# QCopterMV_CAMSPI_Sch.net
KiCad netlist of a schematic drawn in Altium Designer
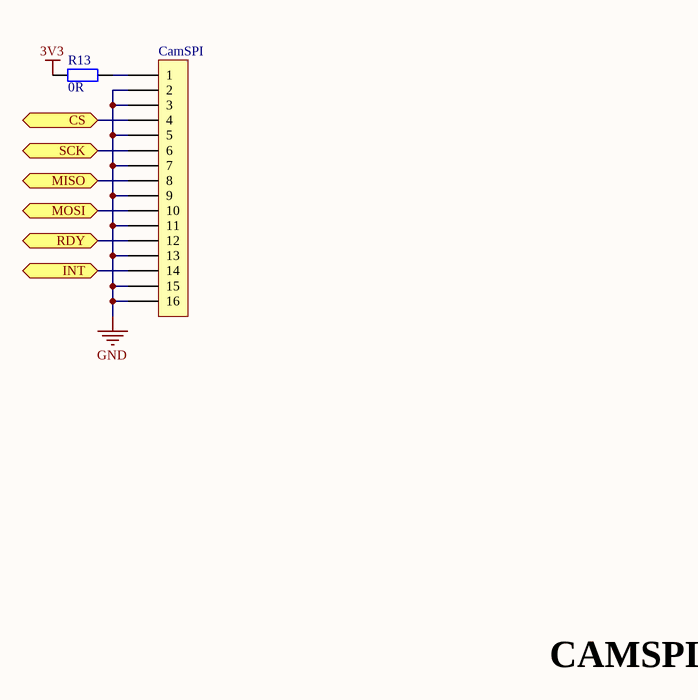
[diagram p0: QCopterMV_CAMSPI_Sch.SchDoc]

(export (version "E")
  (design (tool "Eeschema 10.0.6"))
  (components
    (comp (ref "CamSPI")
      (value "FFC_0.5_16")
      (footprint "PCB_Connector:FFC_0.5_16")
      (description "FFC")
      (libsource (lib "SCH_Connector") (part "FFC_0.5_16"))
    )
    (comp (ref "R13")
      (value "0R")
      (footprint "PCB_Passive:RES_0603")
      (description "Resistor")
      (fields (field (name "Comment") "Res_0603"))
      (libsource (lib "SCH_Passive") (part "Res_0603"))
    )
  )
  (nets
    (net (code "1") (name "/CS") (class "Default")
      (node (ref "CamSPI") (pin "4") (pinfunction "4_4") (pintype "passive"))
    )
    (net (code "2") (name "/INT") (class "Default")
      (node (ref "CamSPI") (pin "14") (pinfunction "14_14") (pintype "passive"))
    )
    (net (code "3") (name "/MISO") (class "Default")
      (node (ref "CamSPI") (pin "8") (pinfunction "8_8") (pintype "passive"))
    )
    (net (code "4") (name "/MOSI") (class "Default")
      (node (ref "CamSPI") (pin "10") (pinfunction "10_10") (pintype "passive"))
    )
    (net (code "5") (name "/RDY") (class "Default")
      (node (ref "CamSPI") (pin "12") (pinfunction "12_12") (pintype "passive"))
    )
    (net (code "6") (name "/SCK") (class "Default")
      (node (ref "CamSPI") (pin "6") (pinfunction "6_6") (pintype "passive"))
    )
    (net (code "7") (name "3V3") (class "Default")
      (node (ref "R13") (pin "1") (pinfunction "1_1") (pintype "passive"))
    )
    (net (code "8") (name "GND") (class "Default")
      (node (ref "CamSPI") (pin "11") (pinfunction "11_11") (pintype "passive"))
      (node (ref "CamSPI") (pin "13") (pinfunction "13_13") (pintype "passive"))
      (node (ref "CamSPI") (pin "15") (pinfunction "15_15") (pintype "passive"))
      (node (ref "CamSPI") (pin "16") (pinfunction "16_16") (pintype "passive"))
      (node (ref "CamSPI") (pin "2") (pinfunction "2_2") (pintype "passive"))
      (node (ref "CamSPI") (pin "3") (pinfunction "3_3") (pintype "passive"))
      (node (ref "CamSPI") (pin "5") (pinfunction "5_5") (pintype "passive"))
      (node (ref "CamSPI") (pin "7") (pinfunction "7_7") (pintype "passive"))
      (node (ref "CamSPI") (pin "9") (pinfunction "9_9") (pintype "passive"))
    )
    (net (code "9") (name "Net-(CamSPI-Pad1)") (class "Default")
      (node (ref "CamSPI") (pin "1") (pinfunction "1_1") (pintype "passive"))
      (node (ref "R13") (pin "2") (pinfunction "2_2") (pintype "passive"))
    )
  )
)
